# front_panel.net
KiCad netlist of a schematic drawn in EAGLE
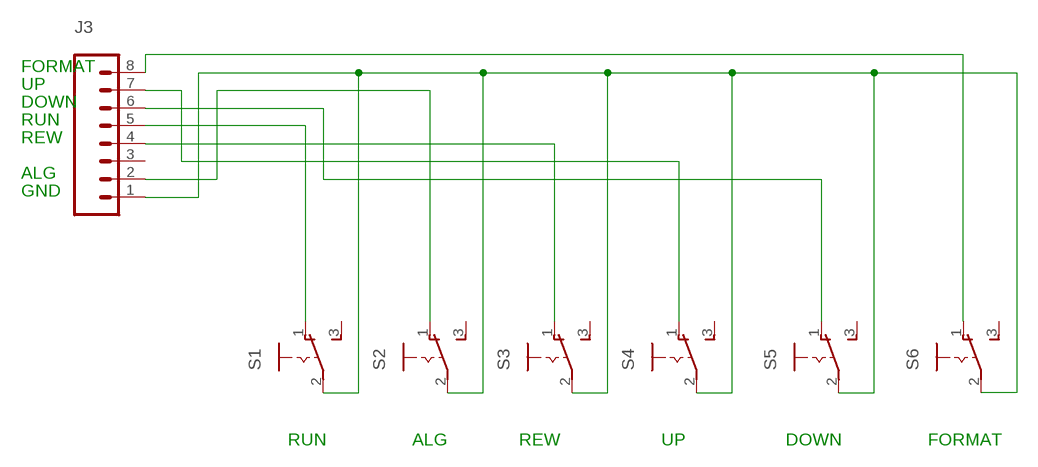
[diagram p0: schematic, sheet 1]

(export (version "E")
  (design (tool "Eeschema 10.0.6"))
  (components
    (comp (ref "J3")
      (value "CONN_08\"")
      (footprint "eagle-import:1X08")
      (libsource (lib "eagle-import") (part "CONN_08{dblquote}"))
    )
    (comp (ref "S1")
      (value "M251")
      (footprint "eagle-import:M251")
      (libsource (lib "eagle-import") (part "M251"))
    )
    (comp (ref "S2")
      (value "M251")
      (footprint "eagle-import:M251")
      (libsource (lib "eagle-import") (part "M251"))
    )
    (comp (ref "S3")
      (value "M251")
      (footprint "eagle-import:M251")
      (libsource (lib "eagle-import") (part "M251"))
    )
    (comp (ref "S4")
      (value "M251")
      (footprint "eagle-import:M251")
      (libsource (lib "eagle-import") (part "M251"))
    )
    (comp (ref "S5")
      (value "M251")
      (footprint "eagle-import:M251")
      (libsource (lib "eagle-import") (part "M251"))
    )
    (comp (ref "S6")
      (value "M251")
      (footprint "eagle-import:M251")
      (libsource (lib "eagle-import") (part "M251"))
    )
  )
  (nets
    (net (code "1") (name "Net-(S1-O)") (class "Default")
      (node (ref "J3") (pin "5") (pinfunction "5_5") (pintype "passive"))
      (node (ref "S1") (pin "1") (pinfunction "O_1") (pintype "passive"))
    )
    (net (code "2") (name "Net-(S1-P)") (class "Default")
      (node (ref "J3") (pin "1") (pinfunction "1_1") (pintype "passive"))
      (node (ref "S1") (pin "2") (pinfunction "P_2") (pintype "passive"))
      (node (ref "S2") (pin "2") (pinfunction "P_2") (pintype "passive"))
      (node (ref "S3") (pin "2") (pinfunction "P_2") (pintype "passive"))
      (node (ref "S4") (pin "2") (pinfunction "P_2") (pintype "passive"))
      (node (ref "S5") (pin "2") (pinfunction "P_2") (pintype "passive"))
      (node (ref "S6") (pin "2") (pinfunction "P_2") (pintype "passive"))
    )
    (net (code "3") (name "Net-(S2-O)") (class "Default")
      (node (ref "J3") (pin "2") (pinfunction "2_2") (pintype "passive"))
      (node (ref "S2") (pin "1") (pinfunction "O_1") (pintype "passive"))
    )
    (net (code "4") (name "Net-(S3-O)") (class "Default")
      (node (ref "J3") (pin "4") (pinfunction "4_4") (pintype "passive"))
      (node (ref "S3") (pin "1") (pinfunction "O_1") (pintype "passive"))
    )
    (net (code "5") (name "Net-(S4-O)") (class "Default")
      (node (ref "J3") (pin "7") (pinfunction "7_7") (pintype "passive"))
      (node (ref "S4") (pin "1") (pinfunction "O_1") (pintype "passive"))
    )
    (net (code "6") (name "Net-(S5-O)") (class "Default")
      (node (ref "J3") (pin "6") (pinfunction "6_6") (pintype "passive"))
      (node (ref "S5") (pin "1") (pinfunction "O_1") (pintype "passive"))
    )
    (net (code "7") (name "Net-(S6-O)") (class "Default")
      (node (ref "J3") (pin "8") (pinfunction "8_8") (pintype "passive"))
      (node (ref "S6") (pin "1") (pinfunction "O_1") (pintype "passive"))
    )
    (net (code "8") (name "unconnected-(J3-Pad3)") (class "Default")
      (node (ref "J3") (pin "3") (pinfunction "3_3") (pintype "passive"))
    )
    (net (code "9") (name "unconnected-(S1-S-Pad3)") (class "Default")
      (node (ref "S1") (pin "3") (pinfunction "S_3") (pintype "passive"))
    )
    (net (code "10") (name "unconnected-(S2-S-Pad3)") (class "Default")
      (node (ref "S2") (pin "3") (pinfunction "S_3") (pintype "passive"))
    )
    (net (code "11") (name "unconnected-(S3-S-Pad3)") (class "Default")
      (node (ref "S3") (pin "3") (pinfunction "S_3") (pintype "passive"))
    )
    (net (code "12") (name "unconnected-(S4-S-Pad3)") (class "Default")
      (node (ref "S4") (pin "3") (pinfunction "S_3") (pintype "passive"))
    )
    (net (code "13") (name "unconnected-(S5-S-Pad3)") (class "Default")
      (node (ref "S5") (pin "3") (pinfunction "S_3") (pintype "passive"))
    )
    (net (code "14") (name "unconnected-(S6-S-Pad3)") (class "Default")
      (node (ref "S6") (pin "3") (pinfunction "S_3") (pintype "passive"))
    )
  )
)
